# USB.net
KiCad netlist of a schematic drawn in Altium Designer
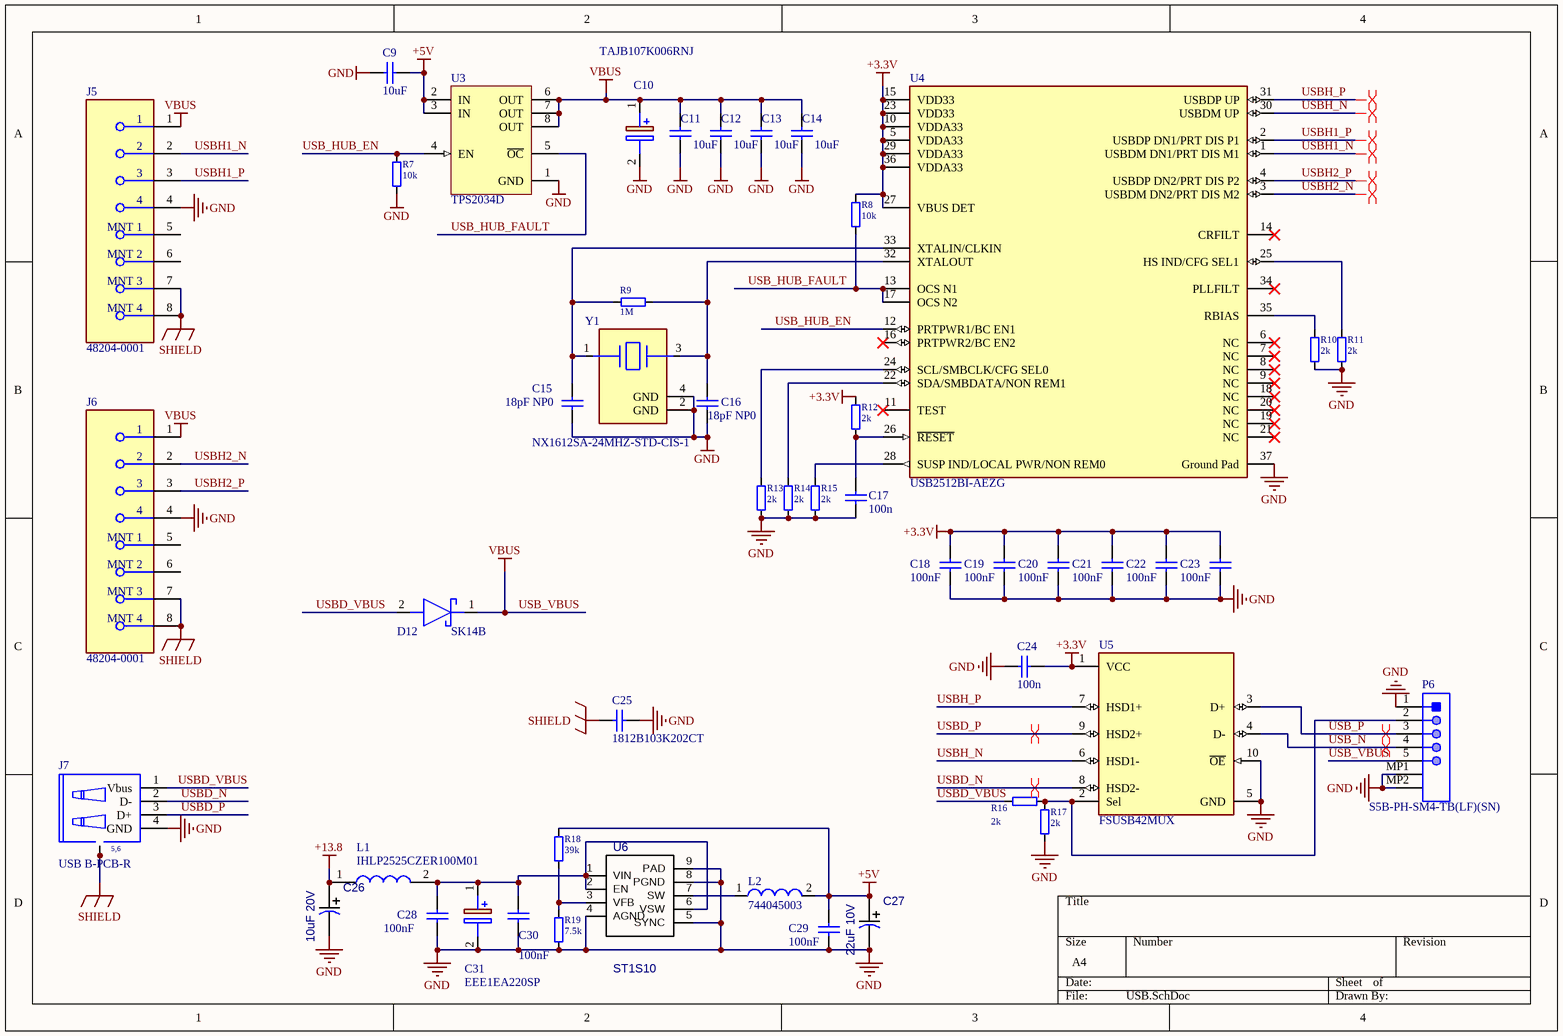
[diagram p0: USB.SchDoc]

(export (version "E")
  (design (tool "Eeschema 10.0.6"))
  (components
    (comp (ref "C9")
      (value "10uF")
      (footprint "C-0805")
      (description "Ceramic Multilayer Capacitor")
      (fields (field (name "MANUFACTURER") "Yageo/Phycomp") (field (name "TOLERANCE") "±10%"))
      (libsource (lib "Hristo") (part "C semi"))
    )
    (comp (ref "C10")
      (value "TAJB107K006RNJ")
      (footprint "SamacSys:CAPPM3528X210N")
      (description "Capacitor Polarised")
      (fields (field (name "MOUSER PART NUMBER") "581-TAJB107K006R"))
      (libsource (lib "*") (part "TAJB107K006RNJ"))
    )
    (comp (ref "C11")
      (value "10uF")
      (footprint "C-0805")
      (description "Ceramic Multilayer Capacitor")
      (fields (field (name "MANUFACTURER") "Yageo/Phycomp") (field (name "TOLERANCE") "±10%"))
      (libsource (lib "Hristo") (part "C semi"))
    )
    (comp (ref "C12")
      (value "10uF")
      (footprint "C-0805")
      (description "Ceramic Multilayer Capacitor")
      (fields (field (name "MANUFACTURER") "Yageo/Phycomp") (field (name "TOLERANCE") "±10%"))
      (libsource (lib "Hristo") (part "C semi"))
    )
    (comp (ref "C13")
      (value "10uF")
      (footprint "C-0805")
      (description "Ceramic Multilayer Capacitor")
      (fields (field (name "MANUFACTURER") "Yageo/Phycomp") (field (name "TOLERANCE") "±10%"))
      (libsource (lib "Hristo") (part "C semi"))
    )
    (comp (ref "C14")
      (value "10uF")
      (footprint "C-0805")
      (description "Ceramic Multilayer Capacitor")
      (fields (field (name "MANUFACTURER") "Yageo/Phycomp") (field (name "TOLERANCE") "±10%"))
      (libsource (lib "Hristo") (part "C semi"))
    )
    (comp (ref "C15")
      (value "18pF NP0")
      (footprint "C-0805")
      (description "Ceramic Multilayer Capacitor")
      (fields (field (name "MANUFACTURER") "Yageo/Phycomp") (field (name "TOLERANCE") "±10%"))
      (libsource (lib "Hristo") (part "C semi"))
    )
    (comp (ref "C16")
      (value "18pF NP0")
      (footprint "C-0805")
      (description "Ceramic Multilayer Capacitor")
      (fields (field (name "MANUFACTURER") "Yageo/Phycomp") (field (name "TOLERANCE") "±10%"))
      (libsource (lib "Hristo") (part "C semi"))
    )
    (comp (ref "C17")
      (value "100n")
      (footprint "C-0805")
      (description "Ceramic Multilayer Capacitor")
      (fields (field (name "MANUFACTURER") "Yageo/Phycomp") (field (name "TOLERANCE") "±10%"))
      (libsource (lib "Hristo") (part "C semi"))
    )
    (comp (ref "C18")
      (value "100nF")
      (footprint "C-0805")
      (description "Ceramic Multilayer Capacitor")
      (fields (field (name "MANUFACTURER") "Yageo/Phycomp") (field (name "TOLERANCE") "±10%"))
      (libsource (lib "Hristo") (part "C semi"))
    )
    (comp (ref "C19")
      (value "100nF")
      (footprint "C-0805")
      (description "Ceramic Multilayer Capacitor")
      (fields (field (name "MANUFACTURER") "Yageo/Phycomp") (field (name "TOLERANCE") "±10%"))
      (libsource (lib "Hristo") (part "C semi"))
    )
    (comp (ref "C20")
      (value "100nF")
      (footprint "C-0805")
      (description "Ceramic Multilayer Capacitor")
      (fields (field (name "MANUFACTURER") "Yageo/Phycomp") (field (name "TOLERANCE") "±10%"))
      (libsource (lib "Hristo") (part "C semi"))
    )
    (comp (ref "C21")
      (value "100nF")
      (footprint "C-0805")
      (description "Ceramic Multilayer Capacitor")
      (fields (field (name "MANUFACTURER") "Yageo/Phycomp") (field (name "TOLERANCE") "±10%"))
      (libsource (lib "Hristo") (part "C semi"))
    )
    (comp (ref "C22")
      (value "100nF")
      (footprint "C-0805")
      (description "Ceramic Multilayer Capacitor")
      (fields (field (name "MANUFACTURER") "Yageo/Phycomp") (field (name "TOLERANCE") "±10%"))
      (libsource (lib "Hristo") (part "C semi"))
    )
    (comp (ref "C23")
      (value "100nF")
      (footprint "C-0805")
      (description "Ceramic Multilayer Capacitor")
      (fields (field (name "MANUFACTURER") "Yageo/Phycomp") (field (name "TOLERANCE") "±10%"))
      (libsource (lib "Hristo") (part "C semi"))
    )
    (comp (ref "C24")
      (value "100n")
      (footprint "C-0805")
      (description "Ceramic Multilayer Capacitor")
      (fields (field (name "MANUFACTURER") "Yageo/Phycomp") (field (name "TOLERANCE") "±10%"))
      (libsource (lib "Hristo") (part "C semi"))
    )
    (comp (ref "C25")
      (value "1812B103K202CT")
      (footprint "CAPC4632X280X75LL50T35")
      (description "X7R ±10% 2kV 10nF 1812 Multilayer Ceramic Capacitors MLCC - SMD/SMT ROHS")
      (fields (field (name "MANUFACTURER") "AVX"))
      (libsource (lib "Altium Content Vault") (part "CAP-NP-2"))
    )
    (comp (ref "C26")
      (value "10uF 20V")
      (footprint "CAPAE_4.3x4.3h5.4")
      (description "CAPAE_4.3x4.3h5.4")
      (libsource (lib "*") (part "CAPAE_4.3x4.3h5.4"))
    )
    (comp (ref "C27")
      (value "22uF 10V")
      (footprint "CAPAE_4.3x4.3h5.4")
      (description "CAPAE_4.3x4.3h5.4")
      (libsource (lib "*") (part "CAPAE_4.3x4.3h5.4"))
    )
    (comp (ref "C28")
      (value "100nF")
      (footprint "C-0805")
      (description "Ceramic Multilayer Capacitor")
      (fields (field (name "MANUFACTURER") "Yageo/Phycomp") (field (name "TOLERANCE") "±10%"))
      (libsource (lib "Hristo") (part "C semi"))
    )
    (comp (ref "C29")
      (value "100nF")
      (footprint "C-0805")
      (description "Ceramic Multilayer Capacitor")
      (fields (field (name "MANUFACTURER") "Yageo/Phycomp") (field (name "TOLERANCE") "±10%"))
      (libsource (lib "Hristo") (part "C semi"))
    )
    (comp (ref "C30")
      (value "100nF")
      (footprint "C-0805")
      (description "Ceramic Multilayer Capacitor")
      (fields (field (name "MANUFACTURER") "Yageo/Phycomp") (field (name "TOLERANCE") "±10%"))
      (libsource (lib "Hristo") (part "C semi"))
    )
    (comp (ref "C31")
      (value "EEE1EA220SP")
      (footprint "SamacSys:EEE1AA101SP")
      (description "Capacitor Polarised")
      (libsource (lib "SamacSys") (part "EEE1EA220SP"))
    )
    (comp (ref "D12")
      (value "SK14B")
      (footprint "SamacSys:DIOM5236X261N")
      (description "Schottky Diode")
      (fields (field (name "MOUSER PART NUMBER") "821-SK14B"))
      (libsource (lib "*") (part "SK14B"))
    )
    (comp (ref "J5")
      (value "48204-0001")
      (footprint "FP-48204-0001-MFG")
      (description "CONN RCPT USB2.0 TYPEA 4POS R/A")
      (libsource (lib "Altium Content Vault") (part "da7372220cc8b30c98743120e27d8b7"))
    )
    (comp (ref "J6")
      (value "48204-0001")
      (footprint "FP-48204-0001-MFG")
      (description "CONN RCPT USB2.0 TYPEA 4POS R/A")
      (libsource (lib "Altium Content Vault") (part "da7372220cc8b30c98743120e27d8b7"))
    )
    (comp (ref "J7")
      (value "USB B-PCB-R")
      (footprint "USB_B_PCB_R")
      (description "Connector USB B-PCB-90 deg")
      (fields (field (name "MANUFACTURER") "SST"))
      (libsource (lib "Hristo") (part "Conn USB 4P"))
    )
    (comp (ref "L1")
      (value "IHLP2525CZER100M01")
      (footprint "SamacSys:INDPM6965X300N")
      (description "Inductor")
      (fields (field (name "MOUSER PART NUMBER") "70-IHLP2525CZER100M0"))
      (libsource (lib "SamacSys") (part "IHLP2525CZER100M01"))
    )
    (comp (ref "L2")
      (value "744045003")
      (footprint "WE-LQ-L")
      (description "SMD-RF-Inductor WE-LQ, L = 3.30 µH")
      (libsource (lib "Altium Content Vault") (part "PAS-IND-INDUCTOR-2"))
    )
    (comp (ref "P6")
      (value "S5B-PH-SM4-TB(LF)(SN)")
      (footprint "JST-S5B-PH-SM4-TB_V")
      (description "Male Header, Pitch 2 mm, 1 x 5 Position, Height 5.5 mm, -25 to 85 degC, RoHS, Tape and Reel")
      (fields (field (name "MANUFACTURER") "JST"))
      (libsource (lib "Altium Content Vault") (part "CN-1P-2M-R5"))
    )
    (comp (ref "R7")
      (value "10k")
      (footprint "R-0805")
      (description "Chip Resistor")
      (fields (field (name "MANUFACTURER") "Yageo/Phycomp"))
      (libsource (lib "Hristo") (part "RES semi"))
    )
    (comp (ref "R8")
      (value "10k")
      (footprint "R-0805")
      (description "Chip Resistor")
      (fields (field (name "MANUFACTURER") "Yageo/Phycomp"))
      (libsource (lib "Hristo") (part "RES semi"))
    )
    (comp (ref "R9")
      (value "1M")
      (footprint "R-0805")
      (description "Chip Resistor")
      (fields (field (name "MANUFACTURER") "Yageo/Phycomp"))
      (libsource (lib "Hristo") (part "RES semi"))
    )
    (comp (ref "R10")
      (value "2k")
      (footprint "R-0805")
      (description "Chip Resistor")
      (fields (field (name "MANUFACTURER") "Yageo/Phycomp"))
      (libsource (lib "Hristo") (part "RES semi"))
    )
    (comp (ref "R11")
      (value "2k")
      (footprint "R-0805")
      (description "Chip Resistor")
      (fields (field (name "MANUFACTURER") "Yageo/Phycomp"))
      (libsource (lib "Hristo") (part "RES semi"))
    )
    (comp (ref "R12")
      (value "2k")
      (footprint "R-0805")
      (description "Chip Resistor")
      (fields (field (name "MANUFACTURER") "Yageo/Phycomp"))
      (libsource (lib "Hristo") (part "RES semi"))
    )
    (comp (ref "R13")
      (value "2k")
      (footprint "R-0805")
      (description "Chip Resistor")
      (fields (field (name "MANUFACTURER") "Yageo/Phycomp"))
      (libsource (lib "Hristo") (part "RES semi"))
    )
    (comp (ref "R14")
      (value "2k")
      (footprint "R-0805")
      (description "Chip Resistor")
      (fields (field (name "MANUFACTURER") "Yageo/Phycomp"))
      (libsource (lib "Hristo") (part "RES semi"))
    )
    (comp (ref "R15")
      (value "2k")
      (footprint "R-0805")
      (description "Chip Resistor")
      (fields (field (name "MANUFACTURER") "Yageo/Phycomp"))
      (libsource (lib "Hristo") (part "RES semi"))
    )
    (comp (ref "R16")
      (value "2k")
      (footprint "R-0805")
      (description "Chip Resistor")
      (fields (field (name "MANUFACTURER") "Yageo/Phycomp"))
      (libsource (lib "Hristo") (part "RES semi"))
    )
    (comp (ref "R17")
      (value "2k")
      (footprint "R-0805")
      (description "Chip Resistor")
      (fields (field (name "MANUFACTURER") "Yageo/Phycomp"))
      (libsource (lib "Hristo") (part "RES semi"))
    )
    (comp (ref "R18")
      (value "39k")
      (footprint "R-0805")
      (description "Chip Resistor")
      (fields (field (name "MANUFACTURER") "Yageo/Phycomp"))
      (libsource (lib "Hristo") (part "RES semi"))
    )
    (comp (ref "R19")
      (value "7.5k")
      (footprint "R-0805")
      (description "Chip Resistor")
      (fields (field (name "MANUFACTURER") "Yageo/Phycomp"))
      (libsource (lib "Hristo") (part "RES semi"))
    )
    (comp (ref "U3")
      (value "TPS2034D")
      (footprint "D0008A_N")
      (fields (field (name "MANUFACTURER") "Texas Instruments"))
      (libsource (lib "Altium Content Vault") (part "TI-TPS2034D8"))
    )
    (comp (ref "U4")
      (value "USB2512BI-AEZG")
      (footprint "FP-USB2512BI-AEZG-MFG")
      (description "IC USB 2.0 2PORT HUB CTLR 36QFN")
      (fields
        (field (name "MANUFACTURER") "Microchip Technology")
        (field (name "OCTOPART") "https://octopart.com/usb2512bi-aezg-microchip-24995415")
      )
      (libsource (lib "Altium Content Vault") (part "5f5d5a1833eed2d4c818db4fedc91ad"))
    )
    (comp (ref "U5")
      (value "FSUSB42MUX")
      (footprint "FP-846AP-MFG")
      (description "IC USB SWITCH DPDT 10MSOP")
      (fields (field (name "VOLTAGE") "4.3V"))
      (libsource (lib "Altium Content Vault") (part "e0bd5e1b4e0e4edc77f3356c64bf8f9"))
    )
    (comp (ref "U6") (value "ST1S10") (footprint "ST1S10") (libsource (lib "*") (part "ST1S10")))
    (comp (ref "Y1")
      (value "NX1612SA-24MHZ-STD-CIS-1")
      (footprint "FP-NX3225GA-MFG")
      (description "CRYSTAL 16.0000MHZ 8PF SMD")
      (libsource (lib "Altium Content Vault") (part "6320effb7d3e443b36bf79d8ebe02e5"))
    )
  )
  (nets
    (net (code "1") (name "+3.3V") (class "Default")
      (node (ref "C18") (pin "1") (pinfunction "1_1") (pintype "passive"))
      (node (ref "C19") (pin "1") (pinfunction "1_1") (pintype "passive"))
      (node (ref "C20") (pin "1") (pinfunction "1_1") (pintype "passive"))
      (node (ref "C21") (pin "1") (pinfunction "1_1") (pintype "passive"))
      (node (ref "C22") (pin "1") (pinfunction "1_1") (pintype "passive"))
      (node (ref "C23") (pin "1") (pinfunction "1_1") (pintype "passive"))
      (node (ref "C24") (pin "2") (pinfunction "2_2") (pintype "passive"))
      (node (ref "R12") (pin "2") (pinfunction "2_2") (pintype "passive"))
      (node (ref "R8") (pin "1") (pinfunction "1_1") (pintype "passive"))
      (node (ref "U4") (pin "10") (pinfunction "VDDA33_10") (pintype "power_in"))
      (node (ref "U4") (pin "15") (pinfunction "VDD33_15") (pintype "power_in"))
      (node (ref "U4") (pin "23") (pinfunction "VDD33_23") (pintype "power_in"))
      (node (ref "U4") (pin "27") (pinfunction "VBUS_DET_27") (pintype "power_in"))
      (node (ref "U4") (pin "29") (pinfunction "VDDA33_29") (pintype "power_in"))
      (node (ref "U4") (pin "36") (pinfunction "VDDA33_36") (pintype "power_in"))
      (node (ref "U4") (pin "5") (pinfunction "VDDA33_5") (pintype "power_in"))
      (node (ref "U5") (pin "1") (pinfunction "VCC_1") (pintype "power_in"))
    )
    (net (code "2") (name "+5V") (class "Default")
      (node (ref "C27") (pin "1") (pinfunction "PLUS_1") (pintype "passive"))
      (node (ref "C29") (pin "1") (pinfunction "1_1") (pintype "passive"))
      (node (ref "C9") (pin "1") (pinfunction "1_1") (pintype "passive"))
      (node (ref "L2") (pin "2") (pinfunction "2_2") (pintype "passive"))
      (node (ref "R18") (pin "1") (pinfunction "1_1") (pintype "passive"))
      (node (ref "U3") (pin "2") (pinfunction "IN_2") (pintype "power_in"))
      (node (ref "U3") (pin "3") (pinfunction "IN_3") (pintype "power_in"))
    )
    (net (code "3") (name "+13.8") (class "Default")
      (node (ref "C26") (pin "1") (pinfunction "PLUS_1") (pintype "passive"))
      (node (ref "L1") (pin "1") (pinfunction "1_1") (pintype "passive"))
    )
    (net (code "4") (name "/USBD_N") (class "Default")
      (node (ref "J7") (pin "2") (pinfunction "D-_2") (pintype "passive"))
      (node (ref "U5") (pin "8") (pinfunction "HSD2-_8") (pintype "bidirectional"))
    )
    (net (code "5") (name "/USBD_P") (class "Default")
      (node (ref "J7") (pin "3") (pinfunction "D+_3") (pintype "passive"))
      (node (ref "U5") (pin "9") (pinfunction "HSD2+_9") (pintype "bidirectional"))
    )
    (net (code "6") (name "/USBD_VBUS") (class "Default")
      (node (ref "D12") (pin "2") (pinfunction "A_2") (pintype "passive"))
      (node (ref "J7") (pin "1") (pinfunction "Vbus_1") (pintype "passive"))
      (node (ref "R16") (pin "2") (pinfunction "2_2") (pintype "passive"))
    )
    (net (code "7") (name "/USBH1_N") (class "Default")
      (node (ref "J5") (pin "2") (pinfunction "2_2") (pintype "passive"))
      (node (ref "U4") (pin "1") (pinfunction "USBDM_DN1/PRT_DIS_M1_1") (pintype "bidirectional"))
    )
    (net (code "8") (name "/USBH1_P") (class "Default")
      (node (ref "J5") (pin "3") (pinfunction "3_3") (pintype "passive"))
      (node (ref "U4") (pin "2") (pinfunction "USBDP_DN1/PRT_DIS_P1_2") (pintype "bidirectional"))
    )
    (net (code "9") (name "/USBH2_N") (class "Default")
      (node (ref "J6") (pin "2") (pinfunction "2_2") (pintype "passive"))
      (node (ref "U4") (pin "3") (pinfunction "USBDM_DN2/PRT_DIS_M2_3") (pintype "bidirectional"))
    )
    (net (code "10") (name "/USBH2_P") (class "Default")
      (node (ref "J6") (pin "3") (pinfunction "3_3") (pintype "passive"))
      (node (ref "U4") (pin "4") (pinfunction "USBDP_DN2/PRT_DIS_P2_4") (pintype "bidirectional"))
    )
    (net (code "11") (name "/USBH_N") (class "Default")
      (node (ref "U4") (pin "30") (pinfunction "USBDM_UP_30") (pintype "bidirectional"))
      (node (ref "U5") (pin "6") (pinfunction "HSD1-_6") (pintype "bidirectional"))
    )
    (net (code "12") (name "/USBH_P") (class "Default")
      (node (ref "U4") (pin "31") (pinfunction "USBDP_UP_31") (pintype "bidirectional"))
      (node (ref "U5") (pin "7") (pinfunction "HSD1+_7") (pintype "bidirectional"))
    )
    (net (code "13") (name "/USB_HUB_EN") (class "Default")
      (node (ref "R7") (pin "2") (pinfunction "2_2") (pintype "passive"))
      (node (ref "U3") (pin "4") (pinfunction "EN_4") (pintype "input"))
      (node (ref "U4") (pin "12") (pinfunction "PRTPWR1/BC_EN1_12") (pintype "bidirectional"))
    )
    (net (code "14") (name "/USB_HUB_FAULT") (class "Default")
      (node (ref "R8") (pin "2") (pinfunction "2_2") (pintype "passive"))
      (node (ref "U3") (pin "5") (pinfunction "~{OC}_5") (pintype "open_collector"))
      (node (ref "U4") (pin "13") (pinfunction "OCS_N1_13") (pintype "passive"))
      (node (ref "U4") (pin "17") (pinfunction "OCS_N2_17") (pintype "passive"))
    )
    (net (code "15") (name "/USB_N") (class "Default")
      (node (ref "P6") (pin "4") (pinfunction "4_4") (pintype "passive"))
      (node (ref "U5") (pin "4") (pinfunction "D-_4") (pintype "bidirectional"))
    )
    (net (code "16") (name "/USB_P") (class "Default")
      (node (ref "P6") (pin "3") (pinfunction "3_3") (pintype "passive"))
      (node (ref "U5") (pin "3") (pinfunction "D+_3") (pintype "bidirectional"))
    )
    (net (code "17") (name "GND") (class "Default")
      (node (ref "C10") (pin "2") (pinfunction "-_2") (pintype "passive"))
      (node (ref "C11") (pin "2") (pinfunction "2_2") (pintype "passive"))
      (node (ref "C12") (pin "2") (pinfunction "2_2") (pintype "passive"))
      (node (ref "C13") (pin "2") (pinfunction "2_2") (pintype "passive"))
      (node (ref "C14") (pin "2") (pinfunction "2_2") (pintype "passive"))
      (node (ref "C15") (pin "1") (pinfunction "1_1") (pintype "passive"))
      (node (ref "C16") (pin "1") (pinfunction "1_1") (pintype "passive"))
      (node (ref "C17") (pin "1") (pinfunction "1_1") (pintype "passive"))
      (node (ref "C18") (pin "2") (pinfunction "2_2") (pintype "passive"))
      (node (ref "C19") (pin "2") (pinfunction "2_2") (pintype "passive"))
      (node (ref "C20") (pin "2") (pinfunction "2_2") (pintype "passive"))
      (node (ref "C21") (pin "2") (pinfunction "2_2") (pintype "passive"))
      (node (ref "C22") (pin "2") (pinfunction "2_2") (pintype "passive"))
      (node (ref "C23") (pin "2") (pinfunction "2_2") (pintype "passive"))
      (node (ref "C24") (pin "1") (pinfunction "1_1") (pintype "passive"))
      (node (ref "C25") (pin "2") (pinfunction "2_2") (pintype "passive"))
      (node (ref "C26") (pin "2") (pinfunction "MINUS_2") (pintype "passive"))
      (node (ref "C27") (pin "2") (pinfunction "MINUS_2") (pintype "passive"))
      (node (ref "C28") (pin "2") (pinfunction "2_2") (pintype "passive"))
      (node (ref "C29") (pin "2") (pinfunction "2_2") (pintype "passive"))
      (node (ref "C30") (pin "2") (pinfunction "2_2") (pintype "passive"))
      (node (ref "C31") (pin "2") (pinfunction "-_2") (pintype "passive"))
      (node (ref "C9") (pin "2") (pinfunction "2_2") (pintype "passive"))
      (node (ref "J5") (pin "4") (pinfunction "4_4") (pintype "passive"))
      (node (ref "J6") (pin "4") (pinfunction "4_4") (pintype "passive"))
      (node (ref "J7") (pin "4") (pinfunction "GND_4") (pintype "passive"))
      (node (ref "P6") (pin "1") (pinfunction "1_1") (pintype "passive"))
      (node (ref "P6") (pin "MP1") (pinfunction "MP1_MP1") (pintype "passive"))
      (node (ref "P6") (pin "MP2") (pinfunction "MP2_MP2") (pintype "passive"))
      (node (ref "R10") (pin "1") (pinfunction "1_1") (pintype "passive"))
      (node (ref "R11") (pin "1") (pinfunction "1_1") (pintype "passive"))
      (node (ref "R13") (pin "1") (pinfunction "1_1") (pintype "passive"))
      (node (ref "R14") (pin "1") (pinfunction "1_1") (pintype "passive"))
      (node (ref "R15") (pin "1") (pinfunction "1_1") (pintype "passive"))
      (node (ref "R17") (pin "1") (pinfunction "1_1") (pintype "passive"))
      (node (ref "R19") (pin "2") (pinfunction "2_2") (pintype "passive"))
      (node (ref "R7") (pin "1") (pinfunction "1_1") (pintype "passive"))
      (node (ref "U3") (pin "1") (pinfunction "GND_1") (pintype "power_in"))
      (node (ref "U4") (pin "37") (pinfunction "Ground_Pad_37") (pintype "power_in"))
      (node (ref "U5") (pin "10") (pinfunction "~{OE}_10") (pintype "input"))
      (node (ref "U5") (pin "5") (pinfunction "GND_5") (pintype "power_in"))
      (node (ref "U6") (pin "4") (pinfunction "AGND_4") (pintype "passive"))
      (node (ref "U6") (pin "5") (pinfunction "SYNC_5") (pintype "passive"))
      (node (ref "U6") (pin "8") (pinfunction "PGND_8") (pintype "passive"))
      (node (ref "U6") (pin "9") (pinfunction "PAD_9") (pintype "passive"))
      (node (ref "Y1") (pin "2") (pinfunction "GND_2") (pintype "power_in"))
      (node (ref "Y1") (pin "4") (pinfunction "GND_4") (pintype "power_in"))
    )
    (net (code "18") (name "Net-(C31-+)") (class "Default")
      (node (ref "C28") (pin "1") (pinfunction "1_1") (pintype "passive"))
      (node (ref "C30") (pin "1") (pinfunction "1_1") (pintype "passive"))
      (node (ref "C31") (pin "1") (pinfunction "+_1") (pintype "passive"))
      (node (ref "L1") (pin "2") (pinfunction "2_2") (pintype "passive"))
      (node (ref "U6") (pin "1") (pinfunction "VIN_1") (pintype "passive"))
      (node (ref "U6") (pin "2") (pinfunction "EN_2") (pintype "passive"))
      (node (ref "U6") (pin "6") (pinfunction "VSW_6") (pintype "passive"))
    )
    (net (code "19") (name "Net-(U4-HS_IND{slash}CFG_SEL1)") (class "Default")
      (node (ref "R11") (pin "2") (pinfunction "2_2") (pintype "passive"))
      (node (ref "U4") (pin "25") (pinfunction "HS_IND/CFG_SEL1_25") (pintype "bidirectional"))
    )
    (net (code "20") (name "Net-(U4-RBIAS)") (class "Default")
      (node (ref "R10") (pin "2") (pinfunction "2_2") (pintype "passive"))
      (node (ref "U4") (pin "35") (pinfunction "RBIAS_35") (pintype "passive"))
    )
    (net (code "21") (name "Net-(U4-SCL{slash}SMBCLK{slash}CFG_SEL0)") (class "Default")
      (node (ref "R13") (pin "2") (pinfunction "2_2") (pintype "passive"))
      (node (ref "U4") (pin "24") (pinfunction "SCL/SMBCLK/CFG_SEL0_24") (pintype "bidirectional"))
    )
    (net (code "22") (name "Net-(U4-SDA{slash}SMBDATA{slash}NON_REM1)") (class "Default")
      (node (ref "R14") (pin "2") (pinfunction "2_2") (pintype "passive"))
      (node (ref "U4") (pin "22") (pinfunction "SDA/SMBDATA/NON_REM1_22") (pintype "bidirectional"))
    )
    (net (code "23") (name "Net-(U4-SUSP_IND{slash}LOCAL_PWR{slash}NON_REM0)") (class "Default")
      (node (ref "R15") (pin "2") (pinfunction "2_2") (pintype "passive"))
      (node (ref "U4") (pin "28") (pinfunction "SUSP_IND/LOCAL_PWR/NON_REM0_28") (pintype "output"))
    )
    (net (code "24") (name "Net-(U4-XTALIN{slash}CLKIN)") (class "Default")
      (node (ref "C15") (pin "2") (pinfunction "2_2") (pintype "passive"))
      (node (ref "R9") (pin "2") (pinfunction "2_2") (pintype "passive"))
      (node (ref "U4") (pin "33") (pinfunction "XTALIN/CLKIN_33") (pintype "passive"))
      (node (ref "Y1") (pin "1") (pinfunction "1_1") (pintype "passive"))
    )
    (net (code "25") (name "Net-(U4-XTALOUT)") (class "Default")
      (node (ref "C16") (pin "2") (pinfunction "2_2") (pintype "passive"))
      (node (ref "R9") (pin "1") (pinfunction "1_1") (pintype "passive"))
      (node (ref "U4") (pin "32") (pinfunction "XTALOUT_32") (pintype "passive"))
      (node (ref "Y1") (pin "3") (pinfunction "3_3") (pintype "passive"))
    )
    (net (code "26") (name "Net-(U4-~{RESET})") (class "Default")
      (node (ref "C17") (pin "2") (pinfunction "2_2") (pintype "passive"))
      (node (ref "R12") (pin "1") (pinfunction "1_1") (pintype "passive"))
      (node (ref "U4") (pin "26") (pinfunction "~{RESET}_26") (pintype "input"))
    )
    (net (code "27") (name "Net-(U5-Sel)") (class "Default")
      (node (ref "P6") (pin "2") (pinfunction "2_2") (pintype "passive"))
      (node (ref "R16") (pin "1") (pinfunction "1_1") (pintype "passive"))
      (node (ref "R17") (pin "2") (pinfunction "2_2") (pintype "passive"))
      (node (ref "U5") (pin "2") (pinfunction "Sel_2") (pintype "passive"))
    )
    (net (code "28") (name "Net-(U6-SW)") (class "Default")
      (node (ref "L2") (pin "1") (pinfunction "1_1") (pintype "passive"))
      (node (ref "U6") (pin "7") (pinfunction "SW_7") (pintype "passive"))
    )
    (net (code "29") (name "Net-(U6-VFB)") (class "Default")
      (node (ref "R18") (pin "2") (pinfunction "2_2") (pintype "passive"))
      (node (ref "R19") (pin "1") (pinfunction "1_1") (pintype "passive"))
      (node (ref "U6") (pin "3") (pinfunction "VFB_3") (pintype "passive"))
    )
    (net (code "30") (name "SHIELD") (class "Default")
      (node (ref "C25") (pin "1") (pinfunction "1_1") (pintype "passive"))
      (node (ref "J5") (pin "7") (pinfunction "MNT_3_7") (pintype "passive"))
      (node (ref "J5") (pin "8") (pinfunction "MNT_4_8") (pintype "passive"))
      (node (ref "J6") (pin "7") (pinfunction "MNT_3_7") (pintype "passive"))
      (node (ref "J6") (pin "8") (pinfunction "MNT_4_8") (pintype "passive"))
      (node (ref "J7") (pin "5") (pinfunction "5_5") (pintype "passive"))
      (node (ref "J7") (pin "6") (pinfunction "6_6") (pintype "passive"))
    )
    (net (code "31") (name "VBUS") (class "Default")
      (node (ref "C10") (pin "1") (pinfunction "+_1") (pintype "passive"))
      (node (ref "C11") (pin "1") (pinfunction "1_1") (pintype "passive"))
      (node (ref "C12") (pin "1") (pinfunction "1_1") (pintype "passive"))
      (node (ref "C13") (pin "1") (pinfunction "1_1") (pintype "passive"))
      (node (ref "C14") (pin "1") (pinfunction "1_1") (pintype "passive"))
      (node (ref "D12") (pin "1") (pinfunction "K_1") (pintype "passive"))
      (node (ref "J5") (pin "1") (pinfunction "1_1") (pintype "passive"))
      (node (ref "J6") (pin "1") (pinfunction "1_1") (pintype "passive"))
      (node (ref "P6") (pin "5") (pinfunction "5_5") (pintype "passive"))
      (node (ref "U3") (pin "6") (pinfunction "OUT_6") (pintype "power_in"))
      (node (ref "U3") (pin "7") (pinfunction "OUT_7") (pintype "power_in"))
      (node (ref "U3") (pin "8") (pinfunction "OUT_8") (pintype "power_in"))
    )
    (net (code "32") (name "unconnected-(J5-MNT_1-Pad5)") (class "Default")
      (node (ref "J5") (pin "5") (pinfunction "MNT_1_5") (pintype "passive"))
    )
    (net (code "33") (name "unconnected-(J5-MNT_2-Pad6)") (class "Default")
      (node (ref "J5") (pin "6") (pinfunction "MNT_2_6") (pintype "passive"))
    )
    (net (code "34") (name "unconnected-(J6-MNT_1-Pad5)") (class "Default")
      (node (ref "J6") (pin "5") (pinfunction "MNT_1_5") (pintype "passive"))
    )
    (net (code "35") (name "unconnected-(J6-MNT_2-Pad6)") (class "Default")
      (node (ref "J6") (pin "6") (pinfunction "MNT_2_6") (pintype "passive"))
    )
    (net (code "36") (name "unconnected-(U4-CRFILT-Pad14)") (class "Default")
      (node (ref "U4") (pin "14") (pinfunction "CRFILT_14") (pintype "passive+no_connect"))
    )
    (net (code "37") (name "unconnected-(U4-NC-Pad6)") (class "Default")
      (node (ref "U4") (pin "6") (pinfunction "NC_6") (pintype "passive+no_connect"))
    )
    (net (code "38") (name "unconnected-(U4-NC-Pad7)") (class "Default")
      (node (ref "U4") (pin "7") (pinfunction "NC_7") (pintype "passive+no_connect"))
    )
    (net (code "39") (name "unconnected-(U4-NC-Pad8)") (class "Default")
      (node (ref "U4") (pin "8") (pinfunction "NC_8") (pintype "passive+no_connect"))
    )
    (net (code "40") (name "unconnected-(U4-NC-Pad9)") (class "Default")
      (node (ref "U4") (pin "9") (pinfunction "NC_9") (pintype "passive+no_connect"))
    )
    (net (code "41") (name "unconnected-(U4-NC-Pad18)") (class "Default")
      (node (ref "U4") (pin "18") (pinfunction "NC_18") (pintype "passive+no_connect"))
    )
    (net (code "42") (name "unconnected-(U4-NC-Pad19)") (class "Default")
      (node (ref "U4") (pin "19") (pinfunction "NC_19") (pintype "passive+no_connect"))
    )
    (net (code "43") (name "unconnected-(U4-NC-Pad20)") (class "Default")
      (node (ref "U4") (pin "20") (pinfunction "NC_20") (pintype "passive+no_connect"))
    )
    (net (code "44") (name "unconnected-(U4-NC-Pad21)") (class "Default")
      (node (ref "U4") (pin "21") (pinfunction "NC_21") (pintype "passive+no_connect"))
    )
    (net (code "45") (name "unconnected-(U4-PLLFILT-Pad34)") (class "Default")
      (node (ref "U4") (pin "34") (pinfunction "PLLFILT_34") (pintype "passive+no_connect"))
    )
    (net (code "46") (name "unconnected-(U4-PRTPWR2{slash}BC_EN2-Pad16)") (class "Default")
      (node (ref "U4") (pin "16") (pinfunction "PRTPWR2/BC_EN2_16") (pintype "bidirectional+no_connect"))
    )
    (net (code "47") (name "unconnected-(U4-TEST-Pad11)") (class "Default")
      (node (ref "U4") (pin "11") (pinfunction "TEST_11") (pintype "passive+no_connect"))
    )
  )
)
